# single_board_controller_copy.net
KiCad netlist of a schematic drawn in EAGLE
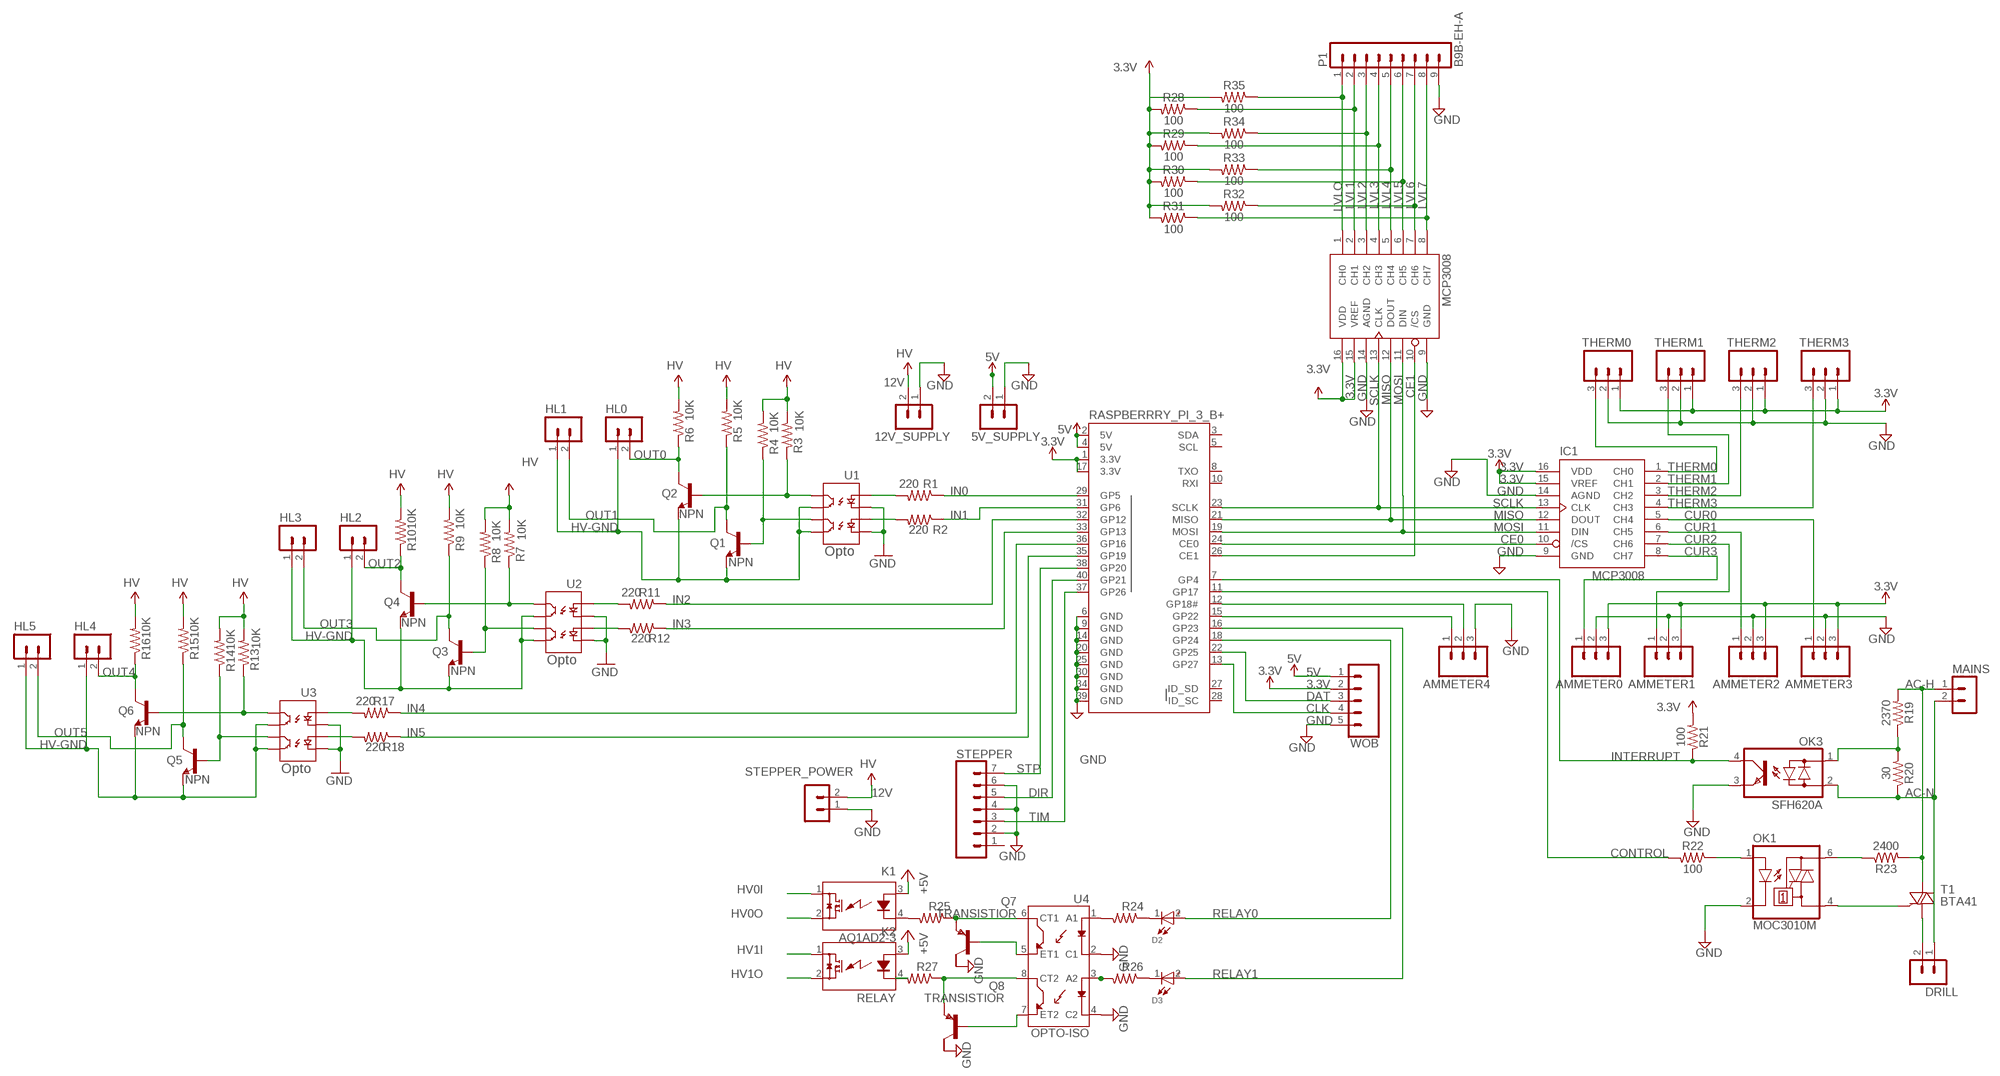
[diagram p0: schematic, sheet 1]

(export (version "E")
  (design (tool "Eeschema 10.0.6"))
  (components
    (comp (ref "5V_SUPPLY")
      (value "B2P-VH")
      (footprint "eagle-import:B2P-VH")
      (libsource (lib "eagle-import") (part "B2P-VH"))
    )
    (comp (ref "12V_SUPPLY")
      (value "B2P-VH")
      (footprint "eagle-import:B2P-VH")
      (libsource (lib "eagle-import") (part "B2P-VH"))
    )
    (comp (ref "AMMETER0")
      (value "CONN_03JST-PTH-VERT")
      (footprint "eagle-import:JST-3-PTH-VERT")
      (libsource (lib "eagle-import") (part "CONN_03JST-PTH-VERT"))
    )
    (comp (ref "AMMETER1")
      (value "CONN_03JST-PTH-VERT")
      (footprint "eagle-import:JST-3-PTH-VERT")
      (libsource (lib "eagle-import") (part "CONN_03JST-PTH-VERT"))
    )
    (comp (ref "AMMETER2")
      (value "CONN_03JST-PTH-VERT")
      (footprint "eagle-import:JST-3-PTH-VERT")
      (libsource (lib "eagle-import") (part "CONN_03JST-PTH-VERT"))
    )
    (comp (ref "AMMETER3")
      (value "CONN_03JST-PTH-VERT")
      (footprint "eagle-import:JST-3-PTH-VERT")
      (libsource (lib "eagle-import") (part "CONN_03JST-PTH-VERT"))
    )
    (comp (ref "AMMETER4")
      (value "CONN_03JST-PTH-VERT")
      (footprint "eagle-import:JST-3-PTH-VERT")
      (libsource (lib "eagle-import") (part "CONN_03JST-PTH-VERT"))
    )
    (comp (ref "D2")
      (value "WL-SMRW_1206_156120YS75000-Y")
      (footprint "eagle-import:WL-SMRW-1206-RECT")
      (libsource (lib "eagle-import") (part "WL-SMRW_1206_156120YS75000-Y"))
    )
    (comp (ref "D3")
      (value "WL-SMRW_1206_156120YS75000-Y")
      (footprint "eagle-import:WL-SMRW-1206-RECT")
      (libsource (lib "eagle-import") (part "WL-SMRW_1206_156120YS75000-Y"))
    )
    (comp (ref "DRILL")
      (value "B2P-VH")
      (footprint "eagle-import:B2P-VH")
      (libsource (lib "eagle-import") (part "B2P-VH"))
    )
    (comp (ref "HL0")
      (value "B2P-VH")
      (footprint "eagle-import:B2P-VH")
      (libsource (lib "eagle-import") (part "B2P-VH"))
    )
    (comp (ref "HL1")
      (value "B2P-VH")
      (footprint "eagle-import:B2P-VH")
      (libsource (lib "eagle-import") (part "B2P-VH"))
    )
    (comp (ref "HL2")
      (value "B2P-VH")
      (footprint "eagle-import:B2P-VH")
      (libsource (lib "eagle-import") (part "B2P-VH"))
    )
    (comp (ref "HL3")
      (value "B2P-VH")
      (footprint "eagle-import:B2P-VH")
      (libsource (lib "eagle-import") (part "B2P-VH"))
    )
    (comp (ref "HL4")
      (value "B2P-VH")
      (footprint "eagle-import:B2P-VH")
      (libsource (lib "eagle-import") (part "B2P-VH"))
    )
    (comp (ref "HL5")
      (value "B2P-VH")
      (footprint "eagle-import:B2P-VH")
      (libsource (lib "eagle-import") (part "B2P-VH"))
    )
    (comp (ref "IC1")
      (value "MCP3008")
      (footprint "eagle-import:DIL16")
      (libsource (lib "eagle-import") (part "MCP3008"))
    )
    (comp (ref "IC2")
      (value "MCP3008")
      (footprint "eagle-import:DIL16")
      (libsource (lib "eagle-import") (part "MCP3008"))
    )
    (comp (ref "K1")
      (value "AQ1AD2-3")
      (footprint "eagle-import:AQ1")
      (fields (field (name "MF") "AROMAT/ MATSUSHITA") (field (name "MPN") "AQ1AD2-3/28VDC"))
      (libsource (lib "eagle-import") (part "AQ1AD2-3"))
    )
    (comp (ref "K2")
      (value "RELAY")
      (footprint "eagle-import:AQ1")
      (fields (field (name "MF") "AROMAT/ MATSUSHITA") (field (name "MPN") "AQ1AD2-3/28VDC"))
      (libsource (lib "eagle-import") (part "AQ1AD2-3"))
    )
    (comp (ref "MAINS")
      (value "B2P-VH")
      (footprint "eagle-import:B2P-VH")
      (libsource (lib "eagle-import") (part "B2P-VH"))
    )
    (comp (ref "OK1")
      (value "MOC3010M")
      (footprint "eagle-import:DIL06")
      (fields (field (name "MF") "FAIRCHILD SEMICONDUCTOR") (field (name "MPN") "MOC3010-M"))
      (libsource (lib "eagle-import") (part "MOC30M10"))
    )
    (comp (ref "OK3")
      (value "SFH620A")
      (footprint "eagle-import:DIL04")
      (fields (field (name "MPN") "SFH620A-2"))
      (libsource (lib "eagle-import") (part "SFH620A"))
    )
    (comp (ref "P1")
      (value "B9B-EH-A")
      (footprint "eagle-import:B9B-EH-A")
      (libsource (lib "eagle-import") (part "B9B-EH-A"))
    )
    (comp (ref "Q1")
      (value "NPN")
      (footprint "eagle-import:SOT23-3")
      (libsource (lib "eagle-import") (part "TRANSISTOR_NPNMMBT2222A"))
    )
    (comp (ref "Q2")
      (value "NPN")
      (footprint "eagle-import:SOT23-3")
      (libsource (lib "eagle-import") (part "TRANSISTOR_NPNMMBT2222A"))
    )
    (comp (ref "Q3")
      (value "NPN")
      (footprint "eagle-import:SOT23-3")
      (libsource (lib "eagle-import") (part "TRANSISTOR_NPNMMBT2222A"))
    )
    (comp (ref "Q4")
      (value "NPN")
      (footprint "eagle-import:SOT23-3")
      (libsource (lib "eagle-import") (part "TRANSISTOR_NPNMMBT2222A"))
    )
    (comp (ref "Q5")
      (value "NPN")
      (footprint "eagle-import:SOT23-3")
      (libsource (lib "eagle-import") (part "TRANSISTOR_NPNMMBT2222A"))
    )
    (comp (ref "Q6")
      (value "NPN")
      (footprint "eagle-import:SOT23-3")
      (libsource (lib "eagle-import") (part "TRANSISTOR_NPNMMBT2222A"))
    )
    (comp (ref "Q7")
      (value "TRANSISTIOR")
      (footprint "eagle-import:SOT89")
      (libsource (lib "eagle-import") (part "PNP-TRANSISTIOR-2COLSOT89"))
    )
    (comp (ref "Q8")
      (value "TRANSISTIOR")
      (footprint "eagle-import:SOT89")
      (libsource (lib "eagle-import") (part "PNP-TRANSISTIOR-2COLSOT89"))
    )
    (comp (ref "R1")
      (value "220")
      (footprint "eagle-import:0603-RES")
      (libsource (lib "eagle-import") (part "220OHM-1/10W-1%(0603)"))
    )
    (comp (ref "R2")
      (value "220")
      (footprint "eagle-import:0603-RES")
      (libsource (lib "eagle-import") (part "220OHM-1/10W-1%(0603)"))
    )
    (comp (ref "R3")
      (value "10K")
      (footprint "eagle-import:0603-RES")
      (libsource (lib "eagle-import") (part "10KOHM1/10W1%(0603)0603"))
    )
    (comp (ref "R4")
      (value "10K")
      (footprint "eagle-import:0603-RES")
      (libsource (lib "eagle-import") (part "10KOHM1/10W1%(0603)0603"))
    )
    (comp (ref "R5")
      (value "10K")
      (footprint "eagle-import:0603-RES")
      (libsource (lib "eagle-import") (part "10KOHM1/10W1%(0603)0603"))
    )
    (comp (ref "R6")
      (value "10K")
      (footprint "eagle-import:0603-RES")
      (libsource (lib "eagle-import") (part "10KOHM1/10W1%(0603)0603"))
    )
    (comp (ref "R7")
      (value "10K")
      (footprint "eagle-import:0603-RES")
      (libsource (lib "eagle-import") (part "10KOHM1/10W1%(0603)0603"))
    )
    (comp (ref "R8")
      (value "10K")
      (footprint "eagle-import:0603-RES")
      (libsource (lib "eagle-import") (part "10KOHM1/10W1%(0603)0603"))
    )
    (comp (ref "R9")
      (value "10K")
      (footprint "eagle-import:0603-RES")
      (libsource (lib "eagle-import") (part "10KOHM1/10W1%(0603)0603"))
    )
    (comp (ref "R10")
      (value "10K")
      (footprint "eagle-import:0603-RES")
      (libsource (lib "eagle-import") (part "10KOHM1/10W1%(0603)0603"))
    )
    (comp (ref "R11")
      (value "220")
      (footprint "eagle-import:0603-RES")
      (libsource (lib "eagle-import") (part "220OHM-1/10W-1%(0603)"))
    )
    (comp (ref "R12")
      (value "220")
      (footprint "eagle-import:0603-RES")
      (libsource (lib "eagle-import") (part "220OHM-1/10W-1%(0603)"))
    )
    (comp (ref "R13")
      (value "10K")
      (footprint "eagle-import:0603-RES")
      (libsource (lib "eagle-import") (part "10KOHM1/10W1%(0603)0603"))
    )
    (comp (ref "R14")
      (value "10K")
      (footprint "eagle-import:0603-RES")
      (libsource (lib "eagle-import") (part "10KOHM1/10W1%(0603)0603"))
    )
    (comp (ref "R15")
      (value "10K")
      (footprint "eagle-import:0603-RES")
      (libsource (lib "eagle-import") (part "10KOHM1/10W1%(0603)0603"))
    )
    (comp (ref "R16")
      (value "10K")
      (footprint "eagle-import:0603-RES")
      (libsource (lib "eagle-import") (part "10KOHM1/10W1%(0603)0603"))
    )
    (comp (ref "R17")
      (value "220")
      (footprint "eagle-import:0603-RES")
      (libsource (lib "eagle-import") (part "220OHM-1/10W-1%(0603)"))
    )
    (comp (ref "R18")
      (value "220")
      (footprint "eagle-import:0603-RES")
      (libsource (lib "eagle-import") (part "220OHM-1/10W-1%(0603)"))
    )
    (comp (ref "R19")
      (value "2370")
      (footprint "eagle-import:0805")
      (libsource (lib "eagle-import") (part "0.3OHM-0805-1/8W-1%"))
    )
    (comp (ref "R20")
      (value "30")
      (footprint "eagle-import:0805")
      (libsource (lib "eagle-import") (part "0.3OHM-0805-1/8W-1%"))
    )
    (comp (ref "R21")
      (value "100")
      (footprint "eagle-import:0805")
      (libsource (lib "eagle-import") (part "0.3OHM-0805-1/8W-1%"))
    )
    (comp (ref "R22")
      (value "100")
      (footprint "eagle-import:0805")
      (libsource (lib "eagle-import") (part "0.3OHM-0805-1/8W-1%"))
    )
    (comp (ref "R23")
      (value "2400")
      (footprint "eagle-import:0805")
      (libsource (lib "eagle-import") (part "0.3OHM-0805-1/8W-1%"))
    )
    (comp (ref "R24")
      (value "FLIPFLOP-RES")
      (footprint "eagle-import:0805-THM")
      (libsource (lib "eagle-import") (part "FLIPFLOP-RES"))
    )
    (comp (ref "R25")
      (value "FLIPFLOP-RES")
      (footprint "eagle-import:0805-THM")
      (libsource (lib "eagle-import") (part "FLIPFLOP-RES"))
    )
    (comp (ref "R26")
      (value "FLIPFLOP-RES")
      (footprint "eagle-import:0805-THM")
      (libsource (lib "eagle-import") (part "FLIPFLOP-RES"))
    )
    (comp (ref "R27")
      (value "FLIPFLOP-RES")
      (footprint "eagle-import:0805-THM")
      (libsource (lib "eagle-import") (part "FLIPFLOP-RES"))
    )
    (comp (ref "R28")
      (value "100")
      (footprint "eagle-import:0805")
      (libsource (lib "eagle-import") (part "0.3OHM-0805-1/8W-1%"))
    )
    (comp (ref "R29")
      (value "100")
      (footprint "eagle-import:0805")
      (libsource (lib "eagle-import") (part "0.3OHM-0805-1/8W-1%"))
    )
    (comp (ref "R30")
      (value "100")
      (footprint "eagle-import:0805")
      (libsource (lib "eagle-import") (part "0.3OHM-0805-1/8W-1%"))
    )
    (comp (ref "R31")
      (value "100")
      (footprint "eagle-import:0805")
      (libsource (lib "eagle-import") (part "0.3OHM-0805-1/8W-1%"))
    )
    (comp (ref "R32")
      (value "100")
      (footprint "eagle-import:0805")
      (libsource (lib "eagle-import") (part "0.3OHM-0805-1/8W-1%"))
    )
    (comp (ref "R33")
      (value "100")
      (footprint "eagle-import:0805")
      (libsource (lib "eagle-import") (part "0.3OHM-0805-1/8W-1%"))
    )
    (comp (ref "R34")
      (value "100")
      (footprint "eagle-import:0805")
      (libsource (lib "eagle-import") (part "0.3OHM-0805-1/8W-1%"))
    )
    (comp (ref "R35")
      (value "100")
      (footprint "eagle-import:0805")
      (libsource (lib "eagle-import") (part "0.3OHM-0805-1/8W-1%"))
    )
    (comp (ref "RASPBERRRY_PI_3_B+")
      (value "RASPBERRYPI-40-PIN-GPIO_PTH_NO_SHROUD")
      (footprint "eagle-import:2X20")
      (libsource (lib "eagle-import") (part "RASPBERRYPI-40-PIN-GPIO_PTH_NO_SHROUD"))
    )
    (comp (ref "STEPPER")
      (value "CONN_07")
      (footprint "eagle-import:1X07")
      (libsource (lib "eagle-import") (part "CONN_07"))
    )
    (comp (ref "STEPPER_POWER")
      (value "B2P-VH")
      (footprint "eagle-import:B2P-VH")
      (libsource (lib "eagle-import") (part "B2P-VH"))
    )
    (comp (ref "T1")
      (value "BTA41")
      (footprint "eagle-import:TOP3L-1")
      (libsource (lib "eagle-import") (part "BTA26-H"))
    )
    (comp (ref "THERM0")
      (value "CONN_03JST-PTH-VERT")
      (footprint "eagle-import:JST-3-PTH-VERT")
      (libsource (lib "eagle-import") (part "CONN_03JST-PTH-VERT"))
    )
    (comp (ref "THERM1")
      (value "CONN_03JST-PTH-VERT")
      (footprint "eagle-import:JST-3-PTH-VERT")
      (libsource (lib "eagle-import") (part "CONN_03JST-PTH-VERT"))
    )
    (comp (ref "THERM2")
      (value "CONN_03JST-PTH-VERT")
      (footprint "eagle-import:JST-3-PTH-VERT")
      (libsource (lib "eagle-import") (part "CONN_03JST-PTH-VERT"))
    )
    (comp (ref "THERM3")
      (value "CONN_03JST-PTH-VERT")
      (footprint "eagle-import:JST-3-PTH-VERT")
      (libsource (lib "eagle-import") (part "CONN_03JST-PTH-VERT"))
    )
    (comp (ref "U1")
      (value "OPTOISOLATOR-2SOIC8")
      (footprint "eagle-import:SO08-2")
      (libsource (lib "eagle-import") (part "OPTOISOLATOR-2SOIC8"))
    )
    (comp (ref "U2")
      (value "OPTOISOLATOR-2SOIC8")
      (footprint "eagle-import:SO08-2")
      (libsource (lib "eagle-import") (part "OPTOISOLATOR-2SOIC8"))
    )
    (comp (ref "U3")
      (value "OPTOISOLATOR-2SOIC8")
      (footprint "eagle-import:SO08-2")
      (libsource (lib "eagle-import") (part "OPTOISOLATOR-2SOIC8"))
    )
    (comp (ref "U4")
      (value "OPTO-ISO")
      (footprint "eagle-import:SO08")
      (libsource (lib "eagle-import") (part "ILD213T-IDL213T"))
    )
    (comp (ref "WOB")
      (value "CONN_05JST-VERT")
      (footprint "eagle-import:JST-5-PTH-VERT")
      (libsource (lib "eagle-import") (part "CONN_05JST-VERT"))
    )
  )
  (nets
    (net (code "1") (name "+5V") (class "Default")
      (node (ref "K1") (pin "3") (pinfunction "A_3") (pintype "passive"))
      (node (ref "K2") (pin "3") (pinfunction "A_3") (pintype "passive"))
    )
    (net (code "2") (name "/AC-H") (class "Default")
      (node (ref "MAINS") (pin "1") (pinfunction "1_1") (pintype "passive"))
      (node (ref "R19") (pin "2") (pinfunction "2_2") (pintype "passive"))
      (node (ref "R23") (pin "2") (pinfunction "2_2") (pintype "passive"))
      (node (ref "T1") (pin "A2") (pinfunction "A2_A2") (pintype "passive"))
    )
    (net (code "3") (name "/AC-N") (class "Default")
      (node (ref "DRILL") (pin "1") (pinfunction "1_1") (pintype "passive"))
      (node (ref "MAINS") (pin "2") (pinfunction "2_2") (pintype "passive"))
      (node (ref "OK3") (pin "2") (pinfunction "AC2_2") (pintype "passive"))
      (node (ref "R20") (pin "1") (pinfunction "1_1") (pintype "passive"))
    )
    (net (code "4") (name "/CE0") (class "Default")
      (node (ref "IC1") (pin "10") (pinfunction "/CS_10") (pintype "input"))
      (node (ref "RASPBERRRY_PI_3_B+") (pin "24") (pinfunction "CE0_24") (pintype "output"))
    )
    (net (code "5") (name "/CE1") (class "Default")
      (node (ref "IC2") (pin "10") (pinfunction "/CS_10") (pintype "input"))
      (node (ref "RASPBERRRY_PI_3_B+") (pin "26") (pinfunction "CE1_26") (pintype "output"))
    )
    (net (code "6") (name "/CLK") (class "Default")
      (node (ref "RASPBERRRY_PI_3_B+") (pin "13") (pinfunction "GP27_13") (pintype "bidirectional"))
      (node (ref "WOB") (pin "4") (pinfunction "4_4") (pintype "passive"))
    )
    (net (code "7") (name "/CONTROL") (class "Default")
      (node (ref "R22") (pin "2") (pinfunction "2_2") (pintype "passive"))
      (node (ref "RASPBERRRY_PI_3_B+") (pin "11") (pinfunction "GP17_11") (pintype "bidirectional"))
    )
    (net (code "8") (name "/CUR0") (class "Default")
      (node (ref "AMMETER3") (pin "1") (pinfunction "1_1") (pintype "passive"))
      (node (ref "IC1") (pin "5") (pinfunction "CH4_5") (pintype "input"))
    )
    (net (code "9") (name "/CUR1") (class "Default")
      (node (ref "AMMETER2") (pin "1") (pinfunction "1_1") (pintype "passive"))
      (node (ref "IC1") (pin "6") (pinfunction "CH5_6") (pintype "input"))
    )
    (net (code "10") (name "/CUR2") (class "Default")
      (node (ref "AMMETER1") (pin "1") (pinfunction "1_1") (pintype "passive"))
      (node (ref "IC1") (pin "7") (pinfunction "CH6_7") (pintype "input"))
    )
    (net (code "11") (name "/CUR3") (class "Default")
      (node (ref "AMMETER0") (pin "1") (pinfunction "1_1") (pintype "passive"))
      (node (ref "IC1") (pin "8") (pinfunction "CH7_8") (pintype "input"))
    )
    (net (code "12") (name "/DAT") (class "Default")
      (node (ref "RASPBERRRY_PI_3_B+") (pin "22") (pinfunction "GP25_22") (pintype "bidirectional"))
      (node (ref "WOB") (pin "3") (pinfunction "3_3") (pintype "passive"))
    )
    (net (code "13") (name "/DIR") (class "Default")
      (node (ref "RASPBERRRY_PI_3_B+") (pin "40") (pinfunction "GP21_40") (pintype "bidirectional"))
      (node (ref "STEPPER") (pin "5") (pinfunction "5_5") (pintype "passive"))
    )
    (net (code "14") (name "/HV-GND") (class "Default")
      (node (ref "HL0") (pin "1") (pinfunction "1_1") (pintype "passive"))
      (node (ref "HL1") (pin "1") (pinfunction "1_1") (pintype "passive"))
      (node (ref "HL2") (pin "1") (pinfunction "1_1") (pintype "passive"))
      (node (ref "HL3") (pin "1") (pinfunction "1_1") (pintype "passive"))
      (node (ref "HL4") (pin "1") (pinfunction "1_1") (pintype "passive"))
      (node (ref "HL5") (pin "1") (pinfunction "1_1") (pintype "passive"))
      (node (ref "Q1") (pin "2") (pinfunction "E_2") (pintype "passive"))
      (node (ref "Q2") (pin "2") (pinfunction "E_2") (pintype "passive"))
      (node (ref "Q3") (pin "2") (pinfunction "E_2") (pintype "passive"))
      (node (ref "Q4") (pin "2") (pinfunction "E_2") (pintype "passive"))
      (node (ref "Q5") (pin "2") (pinfunction "E_2") (pintype "passive"))
      (node (ref "Q6") (pin "2") (pinfunction "E_2") (pintype "passive"))
      (node (ref "U1") (pin "5") (pinfunction "EM2_5") (pintype "bidirectional"))
      (node (ref "U1") (pin "7") (pinfunction "EM1_7") (pintype "bidirectional"))
      (node (ref "U2") (pin "5") (pinfunction "EM2_5") (pintype "bidirectional"))
      (node (ref "U2") (pin "7") (pinfunction "EM1_7") (pintype "bidirectional"))
      (node (ref "U3") (pin "5") (pinfunction "EM2_5") (pintype "bidirectional"))
      (node (ref "U3") (pin "7") (pinfunction "EM1_7") (pintype "bidirectional"))
    )
    (net (code "15") (name "/HV0I") (class "Default")
      (node (ref "K1") (pin "1") (pinfunction "DS1_1") (pintype "passive"))
    )
    (net (code "16") (name "/HV0O") (class "Default")
      (node (ref "K1") (pin "2") (pinfunction "DS2_2") (pintype "passive"))
    )
    (net (code "17") (name "/HV1I") (class "Default")
      (node (ref "K2") (pin "1") (pinfunction "DS1_1") (pintype "passive"))
    )
    (net (code "18") (name "/HV1O") (class "Default")
      (node (ref "K2") (pin "2") (pinfunction "DS2_2") (pintype "passive"))
    )
    (net (code "19") (name "/IN0") (class "Default")
      (node (ref "R1") (pin "1") (pinfunction "1_1") (pintype "passive"))
      (node (ref "RASPBERRRY_PI_3_B+") (pin "29") (pinfunction "GP5_29") (pintype "bidirectional"))
    )
    (net (code "20") (name "/IN1") (class "Default")
      (node (ref "R2") (pin "1") (pinfunction "1_1") (pintype "passive"))
      (node (ref "RASPBERRRY_PI_3_B+") (pin "31") (pinfunction "GP6_31") (pintype "bidirectional"))
    )
    (net (code "21") (name "/IN2") (class "Default")
      (node (ref "R11") (pin "1") (pinfunction "1_1") (pintype "passive"))
      (node (ref "RASPBERRRY_PI_3_B+") (pin "32") (pinfunction "GP12_32") (pintype "bidirectional"))
    )
    (net (code "22") (name "/IN3") (class "Default")
      (node (ref "R12") (pin "1") (pinfunction "1_1") (pintype "passive"))
      (node (ref "RASPBERRRY_PI_3_B+") (pin "33") (pinfunction "GP13_33") (pintype "bidirectional"))
    )
    (net (code "23") (name "/IN4") (class "Default")
      (node (ref "R17") (pin "1") (pinfunction "1_1") (pintype "passive"))
      (node (ref "RASPBERRRY_PI_3_B+") (pin "36") (pinfunction "GP16_36") (pintype "bidirectional"))
    )
    (net (code "24") (name "/IN5") (class "Default")
      (node (ref "R18") (pin "1") (pinfunction "1_1") (pintype "passive"))
      (node (ref "RASPBERRRY_PI_3_B+") (pin "35") (pinfunction "GP19_35") (pintype "bidirectional"))
    )
    (net (code "25") (name "/INTERRUPT") (class "Default")
      (node (ref "OK3") (pin "4") (pinfunction "C_4") (pintype "passive"))
      (node (ref "R21") (pin "1") (pinfunction "1_1") (pintype "passive"))
      (node (ref "RASPBERRRY_PI_3_B+") (pin "7") (pinfunction "GP4_7") (pintype "bidirectional"))
    )
    (net (code "26") (name "/LVL1") (class "Default")
      (node (ref "IC2") (pin "2") (pinfunction "CH1_2") (pintype "input"))
      (node (ref "P1") (pin "2") (pinfunction "2_2") (pintype "passive"))
      (node (ref "R28") (pin "1") (pinfunction "1_1") (pintype "passive"))
    )
    (net (code "27") (name "/LVL2") (class "Default")
      (node (ref "IC2") (pin "3") (pinfunction "CH2_3") (pintype "input"))
      (node (ref "P1") (pin "3") (pinfunction "3_3") (pintype "passive"))
      (node (ref "R34") (pin "1") (pinfunction "1_1") (pintype "passive"))
    )
    (net (code "28") (name "/LVL3") (class "Default")
      (node (ref "IC2") (pin "4") (pinfunction "CH3_4") (pintype "input"))
      (node (ref "P1") (pin "4") (pinfunction "4_4") (pintype "passive"))
      (node (ref "R29") (pin "1") (pinfunction "1_1") (pintype "passive"))
    )
    (net (code "29") (name "/LVL4") (class "Default")
      (node (ref "IC2") (pin "5") (pinfunction "CH4_5") (pintype "input"))
      (node (ref "P1") (pin "5") (pinfunction "5_5") (pintype "passive"))
      (node (ref "R33") (pin "1") (pinfunction "1_1") (pintype "passive"))
    )
    (net (code "30") (name "/LVL5") (class "Default")
      (node (ref "IC2") (pin "6") (pinfunction "CH5_6") (pintype "input"))
      (node (ref "P1") (pin "6") (pinfunction "6_6") (pintype "passive"))
      (node (ref "R30") (pin "1") (pinfunction "1_1") (pintype "passive"))
    )
    (net (code "31") (name "/LVL6") (class "Default")
      (node (ref "IC2") (pin "7") (pinfunction "CH6_7") (pintype "input"))
      (node (ref "P1") (pin "7") (pinfunction "7_7") (pintype "passive"))
      (node (ref "R32") (pin "1") (pinfunction "1_1") (pintype "passive"))
    )
    (net (code "32") (name "/LVL7") (class "Default")
      (node (ref "IC2") (pin "8") (pinfunction "CH7_8") (pintype "input"))
      (node (ref "P1") (pin "8") (pinfunction "8_8") (pintype "passive"))
      (node (ref "R31") (pin "1") (pinfunction "1_1") (pintype "passive"))
    )
    (net (code "33") (name "/LVLO") (class "Default")
      (node (ref "IC2") (pin "1") (pinfunction "CH0_1") (pintype "input"))
      (node (ref "P1") (pin "1") (pinfunction "1_1") (pintype "passive"))
      (node (ref "R35") (pin "1") (pinfunction "1_1") (pintype "passive"))
    )
    (net (code "34") (name "/MISO") (class "Default")
      (node (ref "IC1") (pin "12") (pinfunction "DOUT_12") (pintype "output"))
      (node (ref "IC2") (pin "12") (pinfunction "DOUT_12") (pintype "output"))
      (node (ref "RASPBERRRY_PI_3_B+") (pin "21") (pinfunction "MISO_21") (pintype "input"))
    )
    (net (code "35") (name "/MOSI") (class "Default")
      (node (ref "IC1") (pin "11") (pinfunction "DIN_11") (pintype "input"))
      (node (ref "IC2") (pin "11") (pinfunction "DIN_11") (pintype "input"))
      (node (ref "RASPBERRRY_PI_3_B+") (pin "19") (pinfunction "MOSI_19") (pintype "output"))
    )
    (net (code "36") (name "/OUT0") (class "Default")
      (node (ref "HL0") (pin "2") (pinfunction "2_2") (pintype "passive"))
      (node (ref "Q2") (pin "3") (pinfunction "C_3") (pintype "passive"))
      (node (ref "R6") (pin "1") (pinfunction "1_1") (pintype "passive"))
    )
    (net (code "37") (name "/OUT1") (class "Default")
      (node (ref "HL1") (pin "2") (pinfunction "2_2") (pintype "passive"))
      (node (ref "Q1") (pin "3") (pinfunction "C_3") (pintype "passive"))
      (node (ref "R5") (pin "1") (pinfunction "1_1") (pintype "passive"))
    )
    (net (code "38") (name "/OUT2") (class "Default")
      (node (ref "HL2") (pin "2") (pinfunction "2_2") (pintype "passive"))
      (node (ref "Q4") (pin "3") (pinfunction "C_3") (pintype "passive"))
      (node (ref "R10") (pin "1") (pinfunction "1_1") (pintype "passive"))
    )
    (net (code "39") (name "/OUT3") (class "Default")
      (node (ref "HL3") (pin "2") (pinfunction "2_2") (pintype "passive"))
      (node (ref "Q3") (pin "3") (pinfunction "C_3") (pintype "passive"))
      (node (ref "R9") (pin "1") (pinfunction "1_1") (pintype "passive"))
    )
    (net (code "40") (name "/OUT4") (class "Default")
      (node (ref "HL4") (pin "2") (pinfunction "2_2") (pintype "passive"))
      (node (ref "Q6") (pin "3") (pinfunction "C_3") (pintype "passive"))
      (node (ref "R16") (pin "1") (pinfunction "1_1") (pintype "passive"))
    )
    (net (code "41") (name "/OUT5") (class "Default")
      (node (ref "HL5") (pin "2") (pinfunction "2_2") (pintype "passive"))
      (node (ref "Q5") (pin "3") (pinfunction "C_3") (pintype "passive"))
      (node (ref "R15") (pin "1") (pinfunction "1_1") (pintype "passive"))
    )
    (net (code "42") (name "/RELAY0") (class "Default")
      (node (ref "D2") (pin "2") (pinfunction "+_2") (pintype "passive"))
      (node (ref "RASPBERRRY_PI_3_B+") (pin "18") (pinfunction "GP24_18") (pintype "bidirectional"))
    )
    (net (code "43") (name "/RELAY1") (class "Default")
      (node (ref "D3") (pin "2") (pinfunction "+_2") (pintype "passive"))
      (node (ref "RASPBERRRY_PI_3_B+") (pin "16") (pinfunction "GP23_16") (pintype "bidirectional"))
    )
    (net (code "44") (name "/SCLK") (class "Default")
      (node (ref "IC1") (pin "13") (pinfunction "CLK_13") (pintype "input"))
      (node (ref "IC2") (pin "13") (pinfunction "CLK_13") (pintype "input"))
      (node (ref "RASPBERRRY_PI_3_B+") (pin "23") (pinfunction "SCLK_23") (pintype "output"))
    )
    (net (code "45") (name "/STP") (class "Default")
      (node (ref "RASPBERRRY_PI_3_B+") (pin "38") (pinfunction "GP20_38") (pintype "bidirectional"))
      (node (ref "STEPPER") (pin "7") (pinfunction "7_7") (pintype "passive"))
    )
    (net (code "46") (name "/THERM0") (class "Default")
      (node (ref "IC1") (pin "1") (pinfunction "CH0_1") (pintype "input"))
      (node (ref "THERM0") (pin "3") (pinfunction "3_3") (pintype "passive"))
    )
    (net (code "47") (name "/THERM1") (class "Default")
      (node (ref "IC1") (pin "2") (pinfunction "CH1_2") (pintype "input"))
      (node (ref "THERM1") (pin "3") (pinfunction "3_3") (pintype "passive"))
    )
    (net (code "48") (name "/THERM2") (class "Default")
      (node (ref "IC1") (pin "3") (pinfunction "CH2_3") (pintype "input"))
      (node (ref "THERM2") (pin "3") (pinfunction "3_3") (pintype "passive"))
    )
    (net (code "49") (name "/THERM3") (class "Default")
      (node (ref "IC1") (pin "4") (pinfunction "CH3_4") (pintype "input"))
      (node (ref "THERM3") (pin "3") (pinfunction "3_3") (pintype "passive"))
    )
    (net (code "50") (name "/TIM") (class "Default")
      (node (ref "RASPBERRRY_PI_3_B+") (pin "37") (pinfunction "GP26_37") (pintype "bidirectional"))
      (node (ref "STEPPER") (pin "3") (pinfunction "3_3") (pintype "passive"))
    )
    (net (code "51") (name "3.3V") (class "Default")
      (node (ref "AMMETER0") (pin "3") (pinfunction "3_3") (pintype "passive"))
      (node (ref "AMMETER1") (pin "3") (pinfunction "3_3") (pintype "passive"))
      (node (ref "AMMETER2") (pin "3") (pinfunction "3_3") (pintype "passive"))
      (node (ref "AMMETER3") (pin "3") (pinfunction "3_3") (pintype "passive"))
      (node (ref "IC1") (pin "15") (pinfunction "VREF_15") (pintype "input"))
      (node (ref "IC1") (pin "16") (pinfunction "VDD_16") (pintype "power_in"))
      (node (ref "IC2") (pin "15") (pinfunction "VREF_15") (pintype "input"))
      (node (ref "IC2") (pin "16") (pinfunction "VDD_16") (pintype "power_in"))
      (node (ref "R21") (pin "2") (pinfunction "2_2") (pintype "passive"))
      (node (ref "R28") (pin "2") (pinfunction "2_2") (pintype "passive"))
      (node (ref "R29") (pin "2") (pinfunction "2_2") (pintype "passive"))
      (node (ref "R30") (pin "2") (pinfunction "2_2") (pintype "passive"))
      (node (ref "R31") (pin "2") (pinfunction "2_2") (pintype "passive"))
      (node (ref "R32") (pin "2") (pinfunction "2_2") (pintype "passive"))
      (node (ref "R33") (pin "2") (pinfunction "2_2") (pintype "passive"))
      (node (ref "R34") (pin "2") (pinfunction "2_2") (pintype "passive"))
      (node (ref "R35") (pin "2") (pinfunction "2_2") (pintype "passive"))
      (node (ref "RASPBERRRY_PI_3_B+") (pin "1") (pinfunction "3.3V_1") (pintype "power_in"))
      (node (ref "RASPBERRRY_PI_3_B+") (pin "17") (pinfunction "3.3V_17") (pintype "power_in"))
      (node (ref "THERM0") (pin "1") (pinfunction "1_1") (pintype "passive"))
      (node (ref "THERM1") (pin "1") (pinfunction "1_1") (pintype "passive"))
      (node (ref "THERM2") (pin "1") (pinfunction "1_1") (pintype "passive"))
      (node (ref "THERM3") (pin "1") (pinfunction "1_1") (pintype "passive"))
      (node (ref "WOB") (pin "2") (pinfunction "2_2") (pintype "passive"))
    )
    (net (code "52") (name "5V") (class "Default")
      (node (ref "5V_SUPPLY") (pin "2") (pinfunction "2_2") (pintype "passive"))
      (node (ref "RASPBERRRY_PI_3_B+") (pin "2") (pinfunction "5V_2") (pintype "power_in"))
      (node (ref "RASPBERRRY_PI_3_B+") (pin "4") (pinfunction "5V_4") (pintype "power_in"))
      (node (ref "WOB") (pin "1") (pinfunction "1_1") (pintype "passive"))
    )
    (net (code "53") (name "GND") (class "Default")
      (node (ref "12V_SUPPLY") (pin "1") (pinfunction "1_1") (pintype "passive"))
      (node (ref "5V_SUPPLY") (pin "1") (pinfunction "1_1") (pintype "passive"))
      (node (ref "AMMETER0") (pin "2") (pinfunction "2_2") (pintype "passive"))
      (node (ref "AMMETER1") (pin "2") (pinfunction "2_2") (pintype "passive"))
      (node (ref "AMMETER2") (pin "2") (pinfunction "2_2") (pintype "passive"))
      (node (ref "AMMETER3") (pin "2") (pinfunction "2_2") (pintype "passive"))
      (node (ref "AMMETER4") (pin "3") (pinfunction "3_3") (pintype "passive"))
      (node (ref "IC1") (pin "14") (pinfunction "AGND_14") (pintype "power_in"))
      (node (ref "IC1") (pin "9") (pinfunction "GND_9") (pintype "power_in"))
      (node (ref "IC2") (pin "14") (pinfunction "AGND_14") (pintype "power_in"))
      (node (ref "IC2") (pin "9") (pinfunction "GND_9") (pintype "power_in"))
      (node (ref "OK1") (pin "2") (pinfunction "C_2") (pintype "passive"))
      (node (ref "OK3") (pin "3") (pinfunction "E_3") (pintype "passive"))
      (node (ref "P1") (pin "9") (pinfunction "9_9") (pintype "passive"))
      (node (ref "Q7") (pin "2") (pinfunction "C_2") (pintype "passive"))
      (node (ref "Q8") (pin "2") (pinfunction "C_2") (pintype "passive"))
      (node (ref "RASPBERRRY_PI_3_B+") (pin "14") (pinfunction "GND_14") (pintype "power_in"))
      (node (ref "RASPBERRRY_PI_3_B+") (pin "20") (pinfunction "GND_20") (pintype "power_in"))
      (node (ref "RASPBERRRY_PI_3_B+") (pin "25") (pinfunction "GND_25") (pintype "power_in"))
      (node (ref "RASPBERRRY_PI_3_B+") (pin "30") (pinfunction "GND_30") (pintype "power_in"))
      (node (ref "RASPBERRRY_PI_3_B+") (pin "34") (pinfunction "GND_34") (pintype "power_in"))
      (node (ref "RASPBERRRY_PI_3_B+") (pin "39") (pinfunction "GND_39") (pintype "power_in"))
      (node (ref "RASPBERRRY_PI_3_B+") (pin "6") (pinfunction "GND_6") (pintype "power_in"))
      (node (ref "RASPBERRRY_PI_3_B+") (pin "9") (pinfunction "GND_9") (pintype "power_in"))
      (node (ref "STEPPER") (pin "2") (pinfunction "2_2") (pintype "passive"))
      (node (ref "STEPPER") (pin "4") (pinfunction "4_4") (pintype "passive"))
      (node (ref "STEPPER") (pin "6") (pinfunction "6_6") (pintype "passive"))
      (node (ref "STEPPER_POWER") (pin "1") (pinfunction "1_1") (pintype "passive"))
      (node (ref "THERM0") (pin "2") (pinfunction "2_2") (pintype "passive"))
      (node (ref "THERM1") (pin "2") (pinfunction "2_2") (pintype "passive"))
      (node (ref "THERM2") (pin "2") (pinfunction "2_2") (pintype "passive"))
      (node (ref "THERM3") (pin "2") (pinfunction "2_2") (pintype "passive"))
      (node (ref "U1") (pin "2") (pinfunction "C1_2") (pintype "bidirectional"))
      (node (ref "U1") (pin "4") (pinfunction "C2_4") (pintype "bidirectional"))
      (node (ref "U2") (pin "2") (pinfunction "C1_2") (pintype "bidirectional"))
      (node (ref "U2") (pin "4") (pinfunction "C2_4") (pintype "bidirectional"))
      (node (ref "U3") (pin "2") (pinfunction "C1_2") (pintype "bidirectional"))
      (node (ref "U3") (pin "4") (pinfunction "C2_4") (pintype "bidirectional"))
      (node (ref "U4") (pin "2") (pinfunction "C1_2") (pintype "bidirectional"))
      (node (ref "U4") (pin "4") (pinfunction "C2_4") (pintype "bidirectional"))
      (node (ref "WOB") (pin "5") (pinfunction "5_5") (pintype "passive"))
    )
    (net (code "54") (name "HV") (class "Default")
      (node (ref "12V_SUPPLY") (pin "2") (pinfunction "2_2") (pintype "passive"))
      (node (ref "R10") (pin "2") (pinfunction "2_2") (pintype "passive"))
      (node (ref "R13") (pin "2") (pinfunction "2_2") (pintype "passive"))
      (node (ref "R14") (pin "2") (pinfunction "2_2") (pintype "passive"))
      (node (ref "R15") (pin "2") (pinfunction "2_2") (pintype "passive"))
      (node (ref "R16") (pin "2") (pinfunction "2_2") (pintype "passive"))
      (node (ref "R3") (pin "2") (pinfunction "2_2") (pintype "passive"))
      (node (ref "R4") (pin "2") (pinfunction "2_2") (pintype "passive"))
      (node (ref "R5") (pin "2") (pinfunction "2_2") (pintype "passive"))
      (node (ref "R6") (pin "2") (pinfunction "2_2") (pintype "passive"))
      (node (ref "R7") (pin "2") (pinfunction "2_2") (pintype "passive"))
      (node (ref "R8") (pin "2") (pinfunction "2_2") (pintype "passive"))
      (node (ref "R9") (pin "2") (pinfunction "2_2") (pintype "passive"))
      (node (ref "STEPPER_POWER") (pin "2") (pinfunction "2_2") (pintype "passive"))
    )
    (net (code "55") (name "Net-(D2--)") (class "Default")
      (node (ref "D2") (pin "1") (pinfunction "-_1") (pintype "passive"))
      (node (ref "R24") (pin "1") (pinfunction "1_1") (pintype "passive"))
    )
    (net (code "56") (name "Net-(D3--)") (class "Default")
      (node (ref "D3") (pin "1") (pinfunction "-_1") (pintype "passive"))
      (node (ref "R26") (pin "1") (pinfunction "1_1") (pintype "passive"))
    )
    (net (code "57") (name "Net-(DRILL-Pad2)") (class "Default")
      (node (ref "DRILL") (pin "2") (pinfunction "2_2") (pintype "passive"))
      (node (ref "T1") (pin "A1") (pinfunction "A1_A1") (pintype "passive"))
    )
    (net (code "58") (name "Net-(K1-K)") (class "Default")
      (node (ref "K1") (pin "4") (pinfunction "K_4") (pintype "passive"))
      (node (ref "R25") (pin "2") (pinfunction "2_2") (pintype "passive"))
    )
    (net (code "59") (name "Net-(K2-K)") (class "Default")
      (node (ref "K2") (pin "4") (pinfunction "K_4") (pintype "passive"))
      (node (ref "R27") (pin "2") (pinfunction "2_2") (pintype "passive"))
    )
    (net (code "60") (name "Net-(OK1-A)") (class "Default")
      (node (ref "OK1") (pin "1") (pinfunction "A_1") (pintype "passive"))
      (node (ref "R22") (pin "1") (pinfunction "1_1") (pintype "passive"))
    )
    (net (code "61") (name "Net-(OK1-A1)") (class "Default")
      (node (ref "OK1") (pin "4") (pinfunction "A1_4") (pintype "passive"))
      (node (ref "T1") (pin "G") (pinfunction "G_G") (pintype "passive"))
    )
    (net (code "62") (name "Net-(OK1-A2)") (class "Default")
      (node (ref "OK1") (pin "6") (pinfunction "A2_6") (pintype "passive"))
      (node (ref "R23") (pin "1") (pinfunction "1_1") (pintype "passive"))
    )
    (net (code "63") (name "Net-(OK3-AC1)") (class "Default")
      (node (ref "OK3") (pin "1") (pinfunction "AC1_1") (pintype "passive"))
      (node (ref "R19") (pin "1") (pinfunction "1_1") (pintype "passive"))
      (node (ref "R20") (pin "2") (pinfunction "2_2") (pintype "passive"))
    )
    (net (code "64") (name "Net-(Q1-B)") (class "Default")
      (node (ref "Q1") (pin "1") (pinfunction "B_1") (pintype "passive"))
      (node (ref "R4") (pin "1") (pinfunction "1_1") (pintype "passive"))
      (node (ref "U1") (pin "6") (pinfunction "CL2_6") (pintype "bidirectional"))
    )
    (net (code "65") (name "Net-(Q2-B)") (class "Default")
      (node (ref "Q2") (pin "1") (pinfunction "B_1") (pintype "passive"))
      (node (ref "R3") (pin "1") (pinfunction "1_1") (pintype "passive"))
      (node (ref "U1") (pin "8") (pinfunction "CL1_8") (pintype "bidirectional"))
    )
    (net (code "66") (name "Net-(Q3-B)") (class "Default")
      (node (ref "Q3") (pin "1") (pinfunction "B_1") (pintype "passive"))
      (node (ref "R8") (pin "1") (pinfunction "1_1") (pintype "passive"))
      (node (ref "U2") (pin "6") (pinfunction "CL2_6") (pintype "bidirectional"))
    )
    (net (code "67") (name "Net-(Q4-B)") (class "Default")
      (node (ref "Q4") (pin "1") (pinfunction "B_1") (pintype "passive"))
      (node (ref "R7") (pin "1") (pinfunction "1_1") (pintype "passive"))
      (node (ref "U2") (pin "8") (pinfunction "CL1_8") (pintype "bidirectional"))
    )
    (net (code "68") (name "Net-(Q5-B)") (class "Default")
      (node (ref "Q5") (pin "1") (pinfunction "B_1") (pintype "passive"))
      (node (ref "R14") (pin "1") (pinfunction "1_1") (pintype "passive"))
      (node (ref "U3") (pin "6") (pinfunction "CL2_6") (pintype "bidirectional"))
    )
    (net (code "69") (name "Net-(Q6-B)") (class "Default")
      (node (ref "Q6") (pin "1") (pinfunction "B_1") (pintype "passive"))
      (node (ref "R13") (pin "1") (pinfunction "1_1") (pintype "passive"))
      (node (ref "U3") (pin "8") (pinfunction "CL1_8") (pintype "bidirectional"))
    )
    (net (code "70") (name "Net-(Q7-B)") (class "Default")
      (node (ref "Q7") (pin "1") (pinfunction "B_1") (pintype "passive"))
      (node (ref "U4") (pin "5") (pinfunction "ET1_5") (pintype "bidirectional"))
    )
    (net (code "71") (name "Net-(Q7-E)") (class "Default")
      (node (ref "Q7") (pin "3") (pinfunction "E_3") (pintype "passive"))
      (node (ref "R25") (pin "1") (pinfunction "1_1") (pintype "passive"))
      (node (ref "U4") (pin "6") (pinfunction "CT1_6") (pintype "bidirectional"))
    )
    (net (code "72") (name "Net-(Q8-B)") (class "Default")
      (node (ref "Q8") (pin "1") (pinfunction "B_1") (pintype "passive"))
      (node (ref "U4") (pin "7") (pinfunction "ET2_7") (pintype "bidirectional"))
    )
    (net (code "73") (name "Net-(Q8-E)") (class "Default")
      (node (ref "Q8") (pin "3") (pinfunction "E_3") (pintype "passive"))
      (node (ref "R27") (pin "1") (pinfunction "1_1") (pintype "passive"))
      (node (ref "U4") (pin "8") (pinfunction "CT2_8") (pintype "bidirectional"))
    )
    (net (code "74") (name "Net-(RASPBERRRY_PI_3_B+-GP18#)") (class "Default")
      (node (ref "AMMETER4") (pin "2") (pinfunction "2_2") (pintype "passive"))
      (node (ref "RASPBERRRY_PI_3_B+") (pin "12") (pinfunction "GP18#_12") (pintype "bidirectional"))
    )
    (net (code "75") (name "Net-(RASPBERRRY_PI_3_B+-GP22)") (class "Default")
      (node (ref "AMMETER4") (pin "1") (pinfunction "1_1") (pintype "passive"))
      (node (ref "RASPBERRRY_PI_3_B+") (pin "15") (pinfunction "GP22_15") (pintype "bidirectional"))
    )
    (net (code "76") (name "Net-(U1-A1)") (class "Default")
      (node (ref "R1") (pin "2") (pinfunction "2_2") (pintype "passive"))
      (node (ref "U1") (pin "1") (pinfunction "A1_1") (pintype "bidirectional"))
    )
    (net (code "77") (name "Net-(U1-A2)") (class "Default")
      (node (ref "R2") (pin "2") (pinfunction "2_2") (pintype "passive"))
      (node (ref "U1") (pin "3") (pinfunction "A2_3") (pintype "bidirectional"))
    )
    (net (code "78") (name "Net-(U2-A1)") (class "Default")
      (node (ref "R11") (pin "2") (pinfunction "2_2") (pintype "passive"))
      (node (ref "U2") (pin "1") (pinfunction "A1_1") (pintype "bidirectional"))
    )
    (net (code "79") (name "Net-(U2-A2)") (class "Default")
      (node (ref "R12") (pin "2") (pinfunction "2_2") (pintype "passive"))
      (node (ref "U2") (pin "3") (pinfunction "A2_3") (pintype "bidirectional"))
    )
    (net (code "80") (name "Net-(U3-A1)") (class "Default")
      (node (ref "R17") (pin "2") (pinfunction "2_2") (pintype "passive"))
      (node (ref "U3") (pin "1") (pinfunction "A1_1") (pintype "bidirectional"))
    )
    (net (code "81") (name "Net-(U3-A2)") (class "Default")
      (node (ref "R18") (pin "2") (pinfunction "2_2") (pintype "passive"))
      (node (ref "U3") (pin "3") (pinfunction "A2_3") (pintype "bidirectional"))
    )
    (net (code "82") (name "Net-(U4-A1)") (class "Default")
      (node (ref "R24") (pin "2") (pinfunction "2_2") (pintype "passive"))
      (node (ref "U4") (pin "1") (pinfunction "A1_1") (pintype "bidirectional"))
    )
    (net (code "83") (name "Net-(U4-A2)") (class "Default")
      (node (ref "R26") (pin "2") (pinfunction "2_2") (pintype "passive"))
      (node (ref "U4") (pin "3") (pinfunction "A2_3") (pintype "bidirectional"))
    )
    (net (code "84") (name "unconnected-(Q7-C{slash}-Pad2@1)") (class "Default")
      (node (ref "Q7") (pin "2@1") (pinfunction "C/_2@1") (pintype "passive"))
    )
    (net (code "85") (name "unconnected-(Q8-C{slash}-Pad2@1)") (class "Default")
      (node (ref "Q8") (pin "2@1") (pinfunction "C/_2@1") (pintype "passive"))
    )
    (net (code "86") (name "unconnected-(RASPBERRRY_PI_3_B+-ID_SC-Pad28)") (class "Default")
      (node (ref "RASPBERRRY_PI_3_B+") (pin "28") (pinfunction "ID_SC_28") (pintype "bidirectional"))
    )
    (net (code "87") (name "unconnected-(RASPBERRRY_PI_3_B+-ID_SD-Pad27)") (class "Default")
      (node (ref "RASPBERRRY_PI_3_B+") (pin "27") (pinfunction "ID_SD_27") (pintype "bidirectional"))
    )
    (net (code "88") (name "unconnected-(RASPBERRRY_PI_3_B+-RXI-Pad10)") (class "Default")
      (node (ref "RASPBERRRY_PI_3_B+") (pin "10") (pinfunction "RXI_10") (pintype "input"))
    )
    (net (code "89") (name "unconnected-(RASPBERRRY_PI_3_B+-SCL-Pad5)") (class "Default")
      (node (ref "RASPBERRRY_PI_3_B+") (pin "5") (pinfunction "SCL_5") (pintype "bidirectional"))
    )
    (net (code "90") (name "unconnected-(RASPBERRRY_PI_3_B+-SDA-Pad3)") (class "Default")
      (node (ref "RASPBERRRY_PI_3_B+") (pin "3") (pinfunction "SDA_3") (pintype "bidirectional"))
    )
    (net (code "91") (name "unconnected-(RASPBERRRY_PI_3_B+-TXO-Pad8)") (class "Default")
      (node (ref "RASPBERRRY_PI_3_B+") (pin "8") (pinfunction "TXO_8") (pintype "output"))
    )
    (net (code "92") (name "unconnected-(STEPPER-Pad1)") (class "Default")
      (node (ref "STEPPER") (pin "1") (pinfunction "1_1") (pintype "passive"))
    )
  )
)
